# schematics.net
KiCad netlist of a schematic drawn in EasyEDA
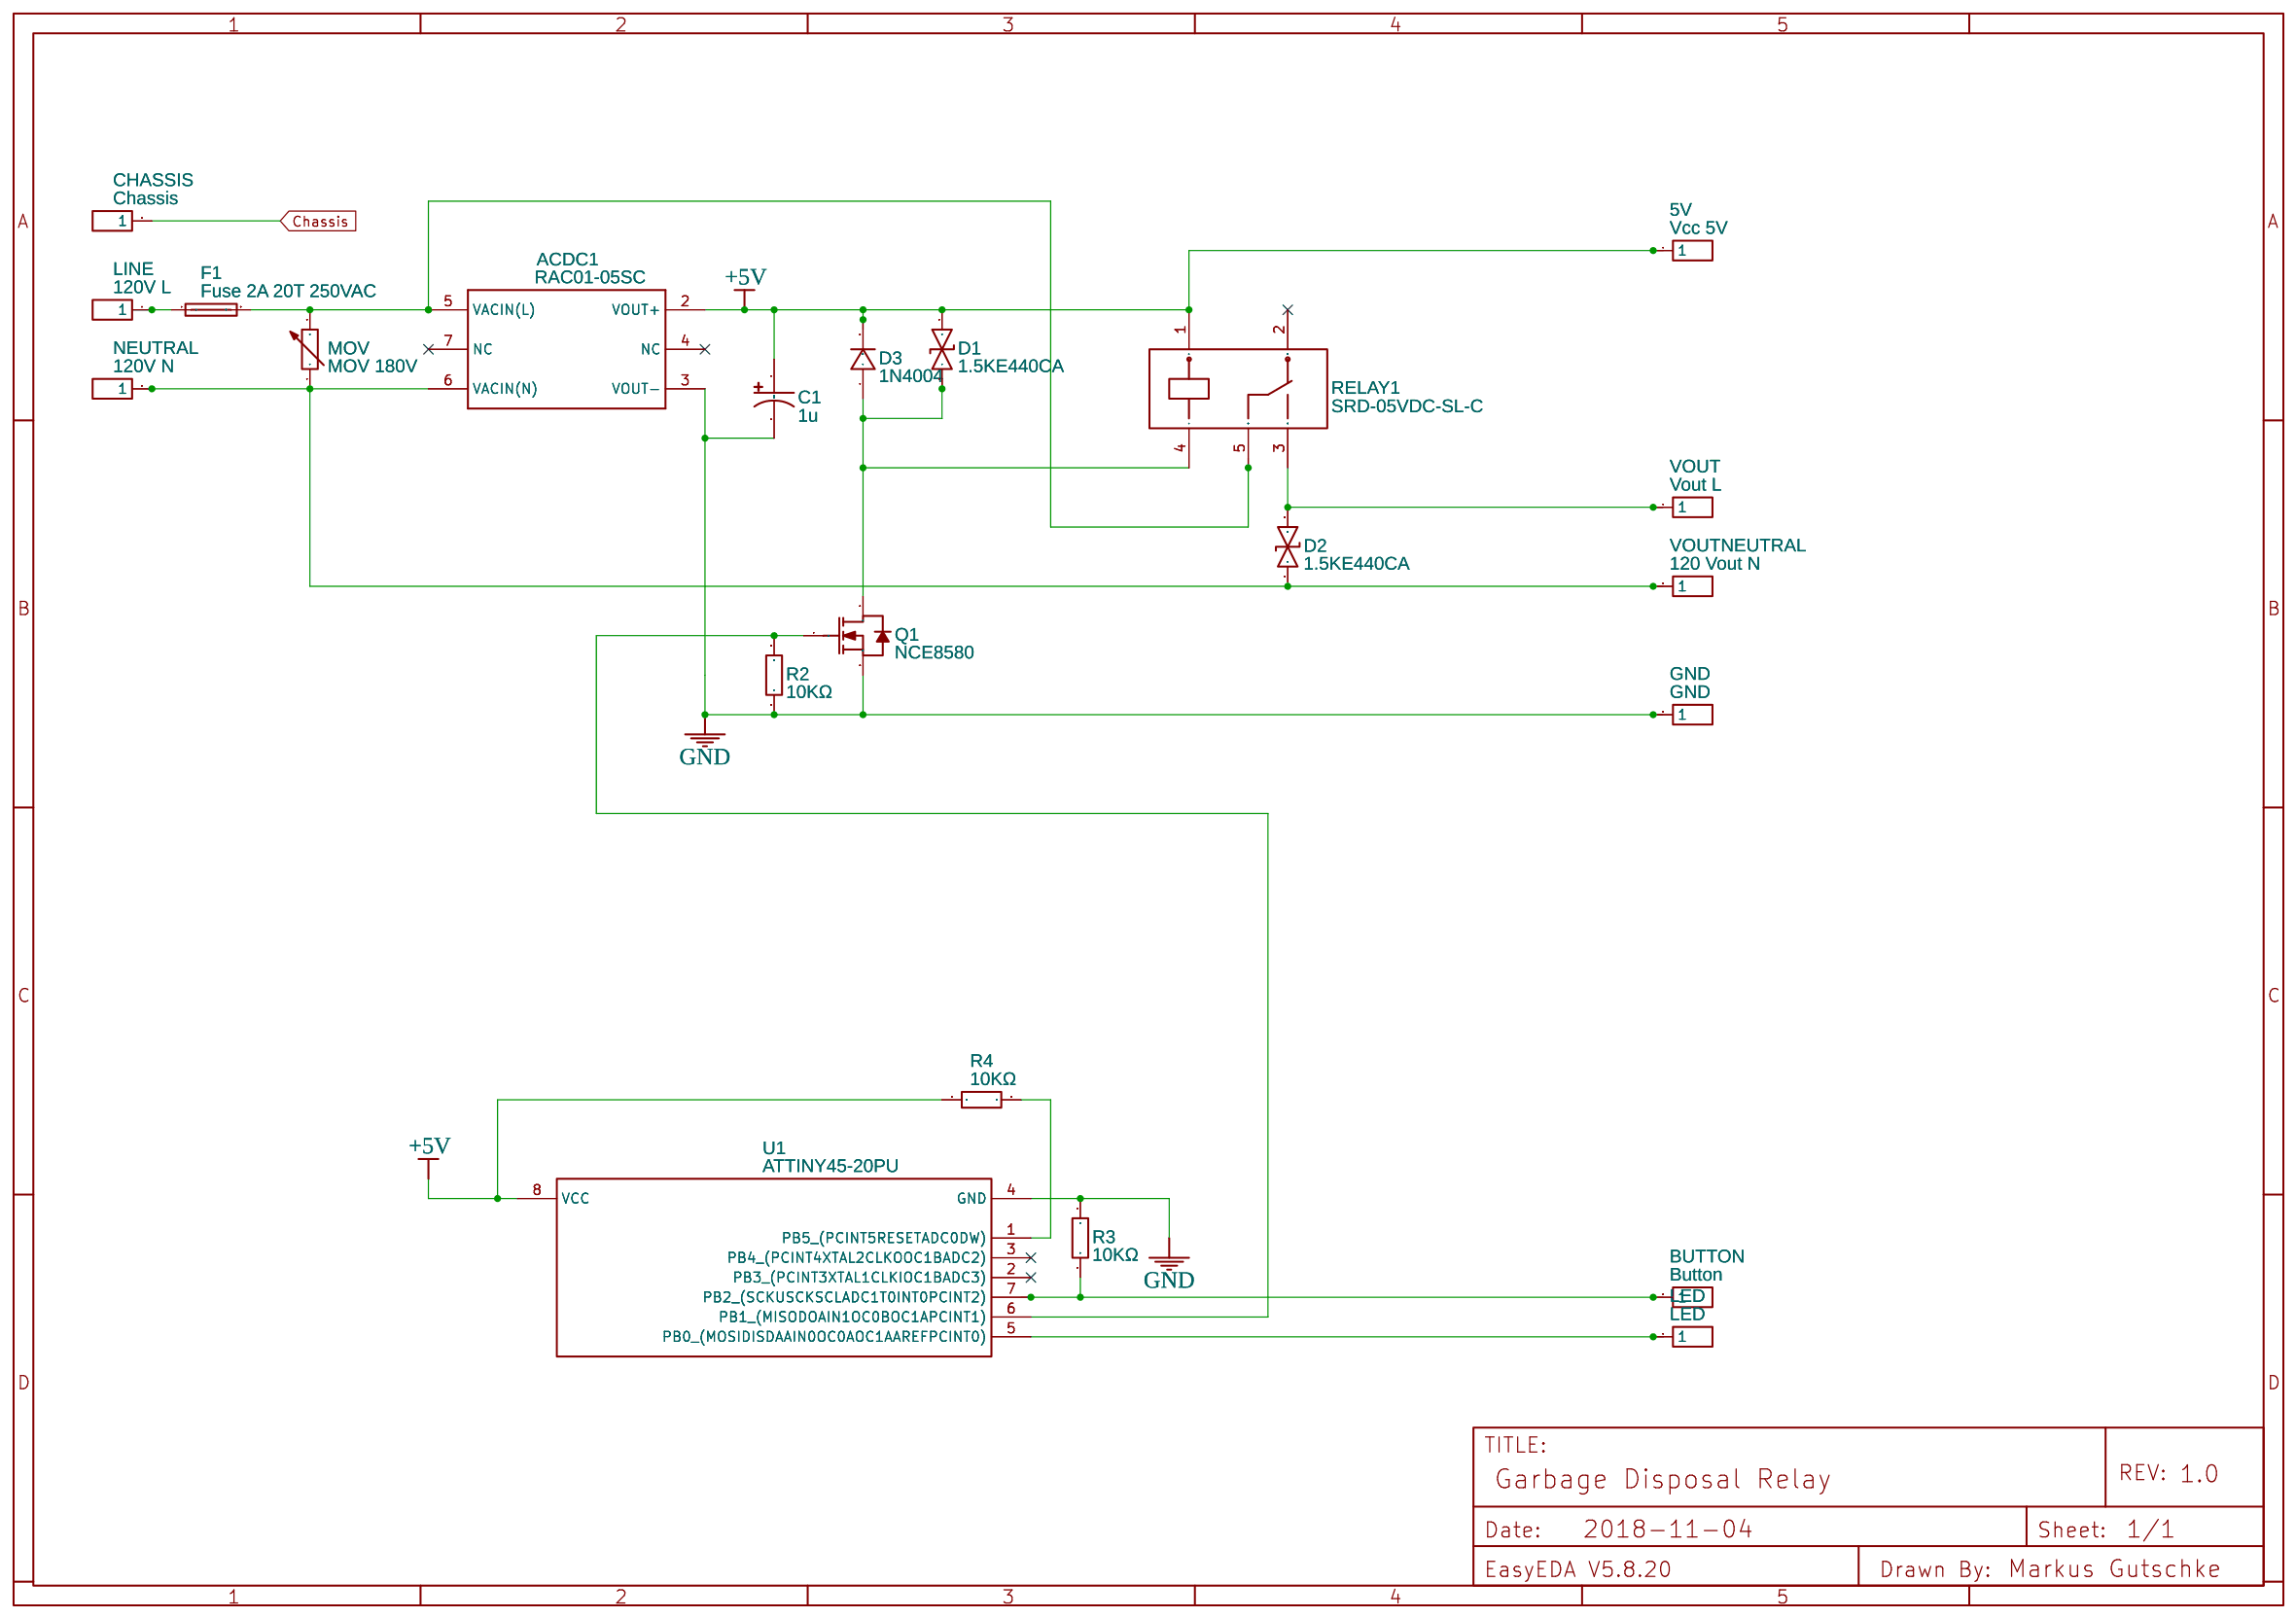
[diagram p0: schematic sheet]

(export (version "E")
  (design (tool "Eeschema 10.0.6"))
  (components
    (comp (ref "5V")
      (value "Vcc 5V")
      (fields
        (field (name "BOM_Manufacturer Part") "1-825433-6")
        (field (name "BOM_Supplier Part") "A122771-ND")
      )
      (libsource (lib "") (part "Unknown_845_120"))
    )
    (comp (ref "ACDC1")
      (value "RAC01-05SC")
      (fields
        (field (name "BOM_Manufacturer Part") "Recom Power")
        (field (name "BOM_Supplier Part") "945-1064-ND")
      )
      (libsource (lib "") (part "Unknown_280_170"))
    )
    (comp (ref "BUTTON")
      (value "Button")
      (fields
        (field (name "BOM_Manufacturer Part") "1-825433-6")
        (field (name "BOM_Supplier Part") "A122771-ND")
      )
      (libsource (lib "") (part "Unknown_845_650"))
    )
    (comp (ref "C1")
      (value "1u")
      (fields
        (field (name "BOM_Manufacturer Part") "TAP105K050SCS")
        (field (name "BOM_Supplier Part") "478-1836-ND")
      )
      (libsource (lib "") (part "Cap_Electrolytic(TH)_D3.0XF1.5_US"))
    )
    (comp (ref "CHASSIS")
      (value "Chassis")
      (fields
        (field (name "BOM_Manufacturer Part") "1-825433-6")
        (field (name "BOM_Supplier Part") "A122771-ND")
      )
      (libsource (lib "") (part "Unknown_55_105"))
    )
    (comp (ref "D1")
      (value "1.5KE440CA")
      (fields
        (field (name "BOM_Manufacturer Part") "1.5KE6.8CA")
        (field (name "BOM_Supplier Part") "1.5KE6.8CALFCT-ND")
      )
      (libsource (lib "") (part "Unknown_470_170"))
    )
    (comp (ref "D2")
      (value "1.5KE440CA")
      (fields
        (field (name "BOM_Manufacturer Part") "1.5KE220CA-TP")
        (field (name "BOM_Supplier Part") "1.5KE220CA-TPMSCT-ND")
      )
      (libsource (lib "") (part "Unknown_645_270"))
    )
    (comp (ref "D3")
      (value "1N4004")
      (fields
        (field (name "BOM_Manufacturer Part") "1N4004-TP")
        (field (name "BOM_Supplier Part") "1N4004-TPMSCT-ND")
      )
      (libsource (lib "") (part "Unknown_430_175"))
    )
    (comp (ref "F1")
      (value "Fuse 2A 20T 250VAC")
      (fields
        (field (name "BOM_Manufacturer Part") "696103201002")
        (field (name "BOM_Supplier Part") "732-11372-ND")
      )
      (libsource (lib "") (part "Unknown_100_150"))
    )
    (comp (ref "GND")
      (value "GND")
      (fields
        (field (name "BOM_Manufacturer Part") "1-825433-6")
        (field (name "BOM_Supplier Part") "A122771-ND")
      )
      (libsource (lib "") (part "Unknown_845_355"))
    )
    (comp (ref "LED")
      (value "LED")
      (fields
        (field (name "BOM_Manufacturer Part") "1-825433-6")
        (field (name "BOM_Supplier Part") "A122771-ND")
      )
      (libsource (lib "") (part "Unknown_845_670"))
    )
    (comp (ref "LINE")
      (value "120V L")
      (fields
        (field (name "BOM_Manufacturer Part") "1-825433-6")
        (field (name "BOM_Supplier Part") "A122771-ND")
      )
      (libsource (lib "") (part "Unknown_55_150"))
    )
    (comp (ref "MOV")
      (value "MOV 180V")
      (fields
        (field (name "BOM_Manufacturer Part") "MOV-14D471KTR")
        (field (name "BOM_Supplier Part") "MOV-14D471KTRCT-ND")
      )
      (libsource (lib "") (part "B72220S0151K101"))
    )
    (comp (ref "NEUTRAL")
      (value "120V N")
      (fields
        (field (name "BOM_Manufacturer Part") "1-825433-6")
        (field (name "BOM_Supplier Part") "A122771-ND")
      )
      (libsource (lib "") (part "Unknown_55_190"))
    )
    (comp (ref "Q1")
      (value "NCE8580")
      (fields
        (field (name "BOM_Manufacturer Part") "HUF76423P3")
        (field (name "BOM_Supplier Part") "HUF76423P3FS-ND")
      )
      (libsource (lib "") (part "Unknown_430_315"))
    )
    (comp (ref "R2")
      (value "10KΩ")
      (fields
        (field (name "BOM_Manufacturer Part") "CFR-25JB-52-10K")
        (field (name "BOM_Supplier Part") "10KQBK-ND")
      )
      (libsource (lib "") (part "CFR0W4J0103A50_1"))
    )
    (comp (ref "R3")
      (value "10KΩ")
      (fields
        (field (name "BOM_Manufacturer Part") "CFR-25JB-52-10K")
        (field (name "BOM_Supplier Part") "10KQBK-ND")
      )
      (libsource (lib "") (part "CFR0W4J0103A50"))
    )
    (comp (ref "R4")
      (value "10KΩ")
      (fields
        (field (name "BOM_Manufacturer Part") "CFR-25JB-52-10K")
        (field (name "BOM_Supplier Part") "10KQBK-ND")
      )
      (libsource (lib "") (part "Res_AXIAL-0.3(1/8W)_EU"))
    )
    (comp (ref "RELAY1")
      (value "SRD-05VDC-SL-C")
      (fields
        (field (name "BOM_Manufacturer Part") "T9GV1L14-5")
        (field (name "BOM_Supplier Part") "PB2362-ND")
      )
      (libsource (lib "") (part "Unknown_625_190"))
    )
    (comp (ref "U1")
      (value "ATTINY45-20PU")
      (fields (field (name "BOM_Supplier Part") "ATTINY45-20PU-ND"))
      (libsource (lib "") (part "Unknown_395_680"))
    )
    (comp (ref "VOUT")
      (value "Vout L")
      (fields
        (field (name "BOM_Manufacturer Part") "1-825433-6")
        (field (name "BOM_Supplier Part") "A122771-ND")
      )
      (libsource (lib "") (part "Unknown_845_250"))
    )
    (comp (ref "VOUTNEUTRAL")
      (value "120 Vout N")
      (fields
        (field (name "BOM_Manufacturer Part") "1-825433-6")
        (field (name "BOM_Supplier Part") "A122771-ND")
      )
      (libsource (lib "") (part "Unknown_845_290"))
    )
  )
  (nets
    (net (code "1") (name "+5V") (class "Default")
      (node (ref "5V") (pin "1") (pinfunction "1_1") (pintype "input"))
      (node (ref "ACDC1") (pin "2") (pinfunction "VOUT+_2") (pintype "passive"))
      (node (ref "C1") (pin "1") (pinfunction "1_1") (pintype "unspecified"))
      (node (ref "D1") (pin "2") (pinfunction "2_2") (pintype "unspecified"))
      (node (ref "D3") (pin "2") (pinfunction "2_2") (pintype "unspecified"))
      (node (ref "R4") (pin "1") (pinfunction "1_1") (pintype "unspecified"))
      (node (ref "RELAY1") (pin "1") (pinfunction "1_1") (pintype "input"))
      (node (ref "U1") (pin "8") (pinfunction "VCC_8") (pintype "passive"))
    )
    (net (code "2") (name "Chassis") (class "Default")
      (node (ref "CHASSIS") (pin "1") (pinfunction "1_1") (pintype "input"))
    )
    (net (code "3") (name "GND") (class "Default")
      (node (ref "ACDC1") (pin "3") (pinfunction "VOUT-_3") (pintype "passive"))
      (node (ref "C1") (pin "2") (pinfunction "2_2") (pintype "unspecified"))
      (node (ref "GND") (pin "1") (pinfunction "1_1") (pintype "input"))
      (node (ref "Q1") (pin "3") (pinfunction "S_3") (pintype "unspecified"))
      (node (ref "R2") (pin "1") (pinfunction "1_1") (pintype "input"))
      (node (ref "R3") (pin "1") (pinfunction "1_1") (pintype "input"))
      (node (ref "U1") (pin "4") (pinfunction "GND_4") (pintype "passive"))
    )
    (net (code "4") (name "Net-(ACDC1-VACIN(L))") (class "Default")
      (node (ref "ACDC1") (pin "5") (pinfunction "VACIN(L)_5") (pintype "passive"))
      (node (ref "F1") (pin "2") (pinfunction "2_2") (pintype "unspecified"))
      (node (ref "MOV") (pin "2") (pinfunction "2_2") (pintype "unspecified"))
      (node (ref "RELAY1") (pin "5") (pinfunction "5_5") (pintype "input"))
    )
    (net (code "5") (name "Net-(ACDC1-VACIN(N))") (class "Default")
      (node (ref "ACDC1") (pin "6") (pinfunction "VACIN(N)_6") (pintype "passive"))
      (node (ref "D2") (pin "1") (pinfunction "1_1") (pintype "unspecified"))
      (node (ref "MOV") (pin "1") (pinfunction "1_1") (pintype "unspecified"))
      (node (ref "NEUTRAL") (pin "1") (pinfunction "1_1") (pintype "input"))
      (node (ref "VOUTNEUTRAL") (pin "1") (pinfunction "1_1") (pintype "input"))
    )
    (net (code "6") (name "Net-(D2-Pad2)") (class "Default")
      (node (ref "D2") (pin "2") (pinfunction "2_2") (pintype "unspecified"))
      (node (ref "RELAY1") (pin "3") (pinfunction "3_3") (pintype "input"))
      (node (ref "VOUT") (pin "1") (pinfunction "1_1") (pintype "input"))
    )
    (net (code "7") (name "Net-(F1-Pad1)") (class "Default")
      (node (ref "F1") (pin "1") (pinfunction "1_1") (pintype "unspecified"))
      (node (ref "LINE") (pin "1") (pinfunction "1_1") (pintype "input"))
    )
    (net (code "8") (name "Net-(Q1-D)") (class "Default")
      (node (ref "D1") (pin "1") (pinfunction "1_1") (pintype "unspecified"))
      (node (ref "D3") (pin "1") (pinfunction "1_1") (pintype "unspecified"))
      (node (ref "Q1") (pin "2") (pinfunction "D_2") (pintype "unspecified"))
      (node (ref "RELAY1") (pin "4") (pinfunction "4_4") (pintype "input"))
    )
    (net (code "9") (name "Net-(Q1-G)") (class "Default")
      (node (ref "Q1") (pin "1") (pinfunction "G_1") (pintype "unspecified"))
      (node (ref "R2") (pin "2") (pinfunction "2_2") (pintype "input"))
      (node (ref "U1") (pin "6") (pinfunction "PB1_(MISODOAIN1OC0BOC1APCINT1)_6") (pintype "bidirectional"))
    )
    (net (code "10") (name "Net-(U1-PB0_(MOSIDISDAAIN0OC0AOC1AAREFPCINT0))") (class "Default")
      (node (ref "LED") (pin "1") (pinfunction "1_1") (pintype "input"))
      (node (ref "U1") (pin "5") (pinfunction "PB0_(MOSIDISDAAIN0OC0AOC1AAREFPCINT0)_5") (pintype "bidirectional"))
    )
    (net (code "11") (name "Net-(U1-PB2_(SCKUSCKSCLADC1T0INT0PCINT2))") (class "Default")
      (node (ref "BUTTON") (pin "1") (pinfunction "1_1") (pintype "input"))
      (node (ref "R3") (pin "2") (pinfunction "2_2") (pintype "input"))
      (node (ref "U1") (pin "7") (pinfunction "PB2_(SCKUSCKSCLADC1T0INT0PCINT2)_7") (pintype "bidirectional"))
    )
    (net (code "12") (name "Net-(U1-PB5_(PCINT5RESETADC0DW))") (class "Default")
      (node (ref "R4") (pin "2") (pinfunction "2_2") (pintype "unspecified"))
      (node (ref "U1") (pin "1") (pinfunction "PB5_(PCINT5RESETADC0DW)_1") (pintype "bidirectional"))
    )
    (net (code "13") (name "unconnected-(ACDC1-NC-Pad4)") (class "Default")
      (node (ref "ACDC1") (pin "4") (pinfunction "NC_4") (pintype "passive+no_connect"))
    )
    (net (code "14") (name "unconnected-(ACDC1-NC-Pad7)") (class "Default")
      (node (ref "ACDC1") (pin "7") (pinfunction "NC_7") (pintype "passive+no_connect"))
    )
    (net (code "15") (name "unconnected-(RELAY1-Pad2)") (class "Default")
      (node (ref "RELAY1") (pin "2") (pinfunction "2_2") (pintype "input+no_connect"))
    )
    (net (code "16") (name "unconnected-(U1-PB3_(PCINT3XTAL1CLKIOC1BADC3)-Pad2)") (class "Default")
      (node (ref "U1") (pin "2") (pinfunction "PB3_(PCINT3XTAL1CLKIOC1BADC3)_2") (pintype "bidirectional+no_connect"))
    )
    (net (code "17") (name "unconnected-(U1-PB4_(PCINT4XTAL2CLKOOC1BADC2)-Pad3)") (class "Default")
      (node (ref "U1") (pin "3") (pinfunction "PB4_(PCINT4XTAL2CLKOOC1BADC2)_3") (pintype "bidirectional+no_connect"))
    )
  )
)
